# Sensor_ExpandBoard_IR.net
KiCad netlist of a schematic drawn in Altium Designer
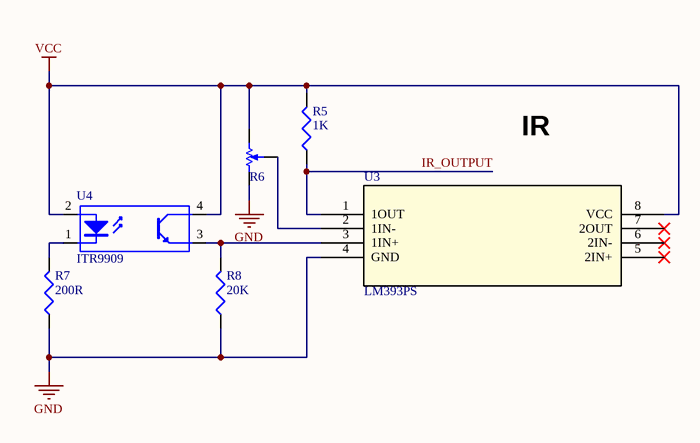
[diagram p0: Sensor_ExpandBoard_IR.SchDoc]

(export (version "E")
  (design (tool "Eeschema 10.0.6"))
  (components
    (comp (ref "R5")
      (value "1K")
      (footprint "R0603")
      (description "Resistor")
      (fields (field (name "PUBLISHER") "Altium Limited"))
      (libsource (lib "step") (part "Res"))
    )
    (comp (ref "R6")
      (value "10K")
      (footprint "POT4MM-2")
      (description "贴片可调电阻，3 x 3，4P")
      (fields (field (name "PUBLISHER") "Altium Limited"))
      (libsource (lib "Miscellaneous Devices") (part "RPot SM"))
    )
    (comp (ref "R7")
      (value "200R")
      (footprint "R0603")
      (description "Resistor")
      (fields (field (name "PUBLISHER") "Altium Limited"))
      (libsource (lib "step") (part "Res"))
    )
    (comp (ref "R8")
      (value "20K")
      (footprint "R0603")
      (description "Resistor")
      (fields (field (name "PUBLISHER") "Altium Limited"))
      (libsource (lib "step") (part "Res"))
    )
    (comp (ref "U3")
      (value "LM393PS")
      (footprint "PS8")
      (description "双路差分比较器LM393")
      (fields (field (name "MANUFACTURER") "Texas Instruments") (field (name "GENERIC_PART_NUMBER") "LM393"))
      (libsource (lib "LM393_PS_8") (part "LM393_PS_8"))
    )
    (comp (ref "U4")
      (value "ITR9909")
      (footprint "IR_PAIRED_TUBE")
      (description "4-Pin Phototransistor Optocoupler")
      (fields (field (name "PUBLISHER") "Altium Limited"))
      (libsource (lib "Sensor") (part "Optoisolator1"))
    )
  )
  (nets
    (net (code "1") (name "/IR_OUTPUT") (class "Default")
      (node (ref "R5") (pin "1") (pinfunction "1_1") (pintype "passive"))
      (node (ref "U3") (pin "1") (pinfunction "1OUT_1") (pintype "passive"))
    )
    (net (code "2") (name "GND") (class "Default")
      (node (ref "R6") (pin "CCW") (pinfunction "-_CCW") (pintype "passive"))
      (node (ref "R7") (pin "1") (pinfunction "1_1") (pintype "passive"))
      (node (ref "R8") (pin "1") (pinfunction "1_1") (pintype "passive"))
      (node (ref "U3") (pin "4") (pinfunction "GND_4") (pintype "passive"))
    )
    (net (code "3") (name "Net-(U3-1IN+)") (class "Default")
      (node (ref "R8") (pin "2") (pinfunction "2_2") (pintype "passive"))
      (node (ref "U3") (pin "3") (pinfunction "1IN+_3") (pintype "passive"))
      (node (ref "U4") (pin "3") (pinfunction "E_3") (pintype "passive"))
    )
    (net (code "4") (name "Net-(U3-1IN-)") (class "Default")
      (node (ref "R6") (pin "W") (pinfunction "W_W") (pintype "passive"))
      (node (ref "U3") (pin "2") (pinfunction "1IN-_2") (pintype "passive"))
    )
    (net (code "5") (name "Net-(U4-K)") (class "Default")
      (node (ref "R7") (pin "2") (pinfunction "2_2") (pintype "passive"))
      (node (ref "U4") (pin "1") (pinfunction "K_1") (pintype "passive"))
    )
    (net (code "6") (name "VCC") (class "Default")
      (node (ref "R5") (pin "2") (pinfunction "2_2") (pintype "passive"))
      (node (ref "R6") (pin "CW") (pinfunction "+_CW") (pintype "passive"))
      (node (ref "U3") (pin "8") (pinfunction "VCC_8") (pintype "passive"))
      (node (ref "U4") (pin "2") (pinfunction "A_2") (pintype "passive"))
      (node (ref "U4") (pin "4") (pinfunction "C_4") (pintype "passive"))
    )
    (net (code "7") (name "unconnected-(U3-2IN+-Pad5)") (class "Default")
      (node (ref "U3") (pin "5") (pinfunction "2IN+_5") (pintype "passive+no_connect"))
    )
    (net (code "8") (name "unconnected-(U3-2IN--Pad6)") (class "Default")
      (node (ref "U3") (pin "6") (pinfunction "2IN-_6") (pintype "passive+no_connect"))
    )
    (net (code "9") (name "unconnected-(U3-2OUT-Pad7)") (class "Default")
      (node (ref "U3") (pin "7") (pinfunction "2OUT_7") (pintype "passive+no_connect"))
    )
  )
)
